# I2C_BUS.net
KiCad netlist of a schematic drawn in Altium Designer
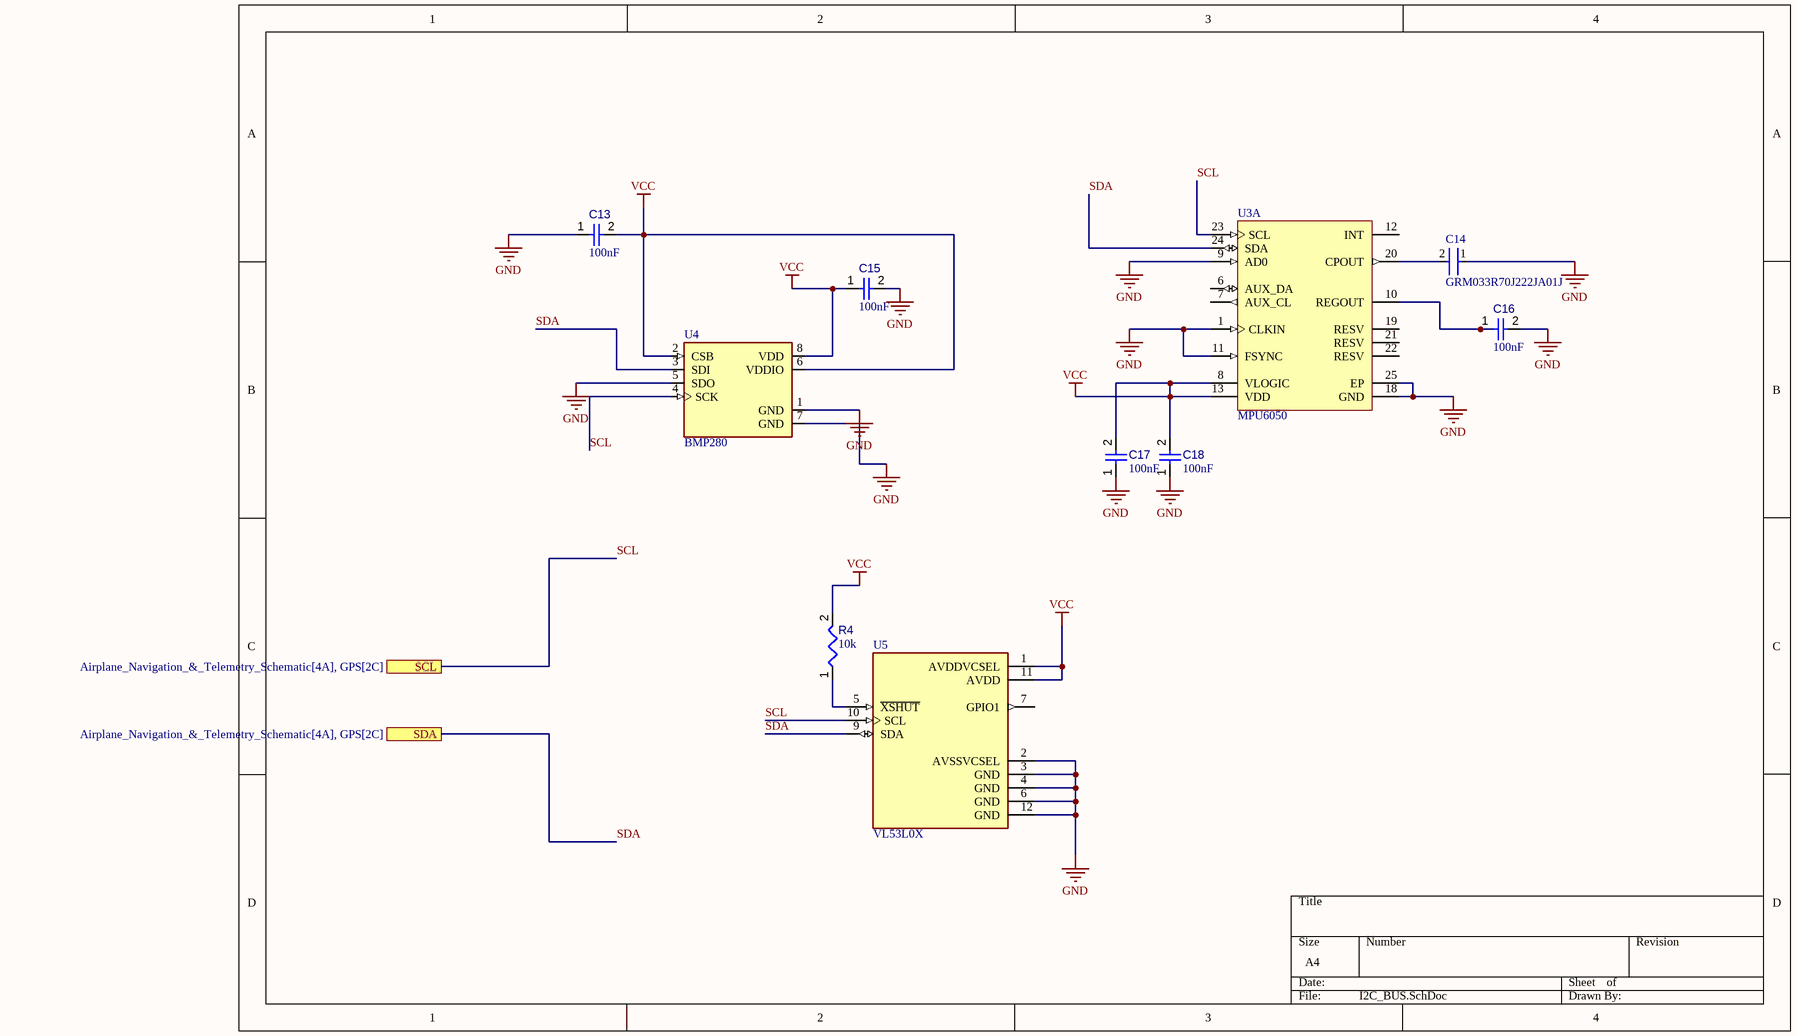
[diagram p0: I2C_BUS.SchDoc]

(export (version "E")
  (design (tool "Eeschema 10.0.6"))
  (components
    (comp (ref "C13")
      (value "100nF")
      (footprint "CAPC0402(1005)60_L")
      (description "Chip Capacitor, 100nF +/-20%, 10V, 0402, Thickness 0.6 mm")
      (fields (field (name "TOLERANCE") "20%") (field (name "Comment") "Capacitor 100nF +/-20% 10V 0402"))
      (libsource (lib "Lachlan Biersteker") (part "CAP-NP-2"))
    )
    (comp (ref "C14")
      (value "GRM033R70J222JA01J")
      (footprint "FP-GRM033-0_03-IPC_B")
      (description "Chip Multilayer Ceramic Capacitors for General Purpose, 0201, 2200pF, X7R, 15%, 5%, 6.3V")
      (fields (field (name "TOLERANCE") "5%"))
      (libsource (lib "Altium Content Vault") (part "b4654b650e69147ec39a6b967a45e02"))
    )
    (comp (ref "C15")
      (value "100nF")
      (footprint "CAPC0402(1005)60_L")
      (description "Chip Capacitor, 100nF +/-20%, 10V, 0402, Thickness 0.6 mm")
      (fields (field (name "TOLERANCE") "20%") (field (name "Comment") "Capacitor 100nF +/-20% 10V 0402"))
      (libsource (lib "Lachlan Biersteker") (part "CAP-NP-2"))
    )
    (comp (ref "C16")
      (value "100nF")
      (footprint "CAPC1005X56X25LL10T15")
      (description "Chip Capacitor, 0.1 uF, +/- 5%, 16 V, 0402 (1005 Metric)")
      (fields (field (name "TOLERANCE") "5%") (field (name "Comment") "Capacitor 0.1 uF +/- 5% 16 V 0402"))
      (libsource (lib "Lachlan Biersteker") (part "CAP-NP-2"))
    )
    (comp (ref "C17")
      (value "100nF")
      (footprint "CAPC0402(1005)60_L")
      (description "Chip Capacitor, 100nF +/-20%, 10V, 0402, Thickness 0.6 mm")
      (fields (field (name "TOLERANCE") "20%") (field (name "Comment") "Capacitor 100nF +/-20% 10V 0402"))
      (libsource (lib "Lachlan Biersteker") (part "CAP-NP-2"))
    )
    (comp (ref "C18")
      (value "100nF")
      (footprint "CAPC0402(1005)60_L")
      (description "Chip Capacitor, 100nF +/-20%, 10V, 0402, Thickness 0.6 mm")
      (fields (field (name "TOLERANCE") "20%") (field (name "Comment") "Capacitor 100nF +/-20% 10V 0402"))
      (libsource (lib "Lachlan Biersteker") (part "CAP-NP-2"))
    )
    (comp (ref "R4")
      (value "10k")
      (footprint "RESC1005X40X25ML05T05")
      (description "Chip Resistor, 10 KOhm, +/- 1%, 0.1 W, -55 to 155 degC, 0402 (1005 Metric)")
      (fields (field (name "TOLERANCE") "1%") (field (name "POWER") "100mW"))
      (libsource (lib "Lachlan Biersteker") (part "RES-2"))
    )
    (comp (ref "U3")
      (value "MPU6050")
      (footprint "INSE-QFN-24_V")
      (fields (field (name "MANUFACTURER") "InvenSense"))
      (libsource (lib "Lachlan Biersteker") (part "INSE-MPU6050-QFN-24"))
    )
    (comp (ref "U4")
      (value "BMP280")
      (footprint "XDCR_BMP280")
      (description "BMP280 Absolute Barometric Pressure Sensor for Battery Powered Devices 2 x 2.5mm")
      (libsource (lib "Lachlan Biersteker") (part "BMP280"))
    )
    (comp (ref "U5")
      (value "VL53L0X")
      (footprint "SENSOR_VL53L0X")
      (description "VL53L0X - Light, 3D Time-of-Flight _ToF_ Sensor Evaluation Board")
      (fields (field (name "MF") "STMicroelectronics"))
      (libsource (lib "Lachlan Biersteker") (part "VL53L0X"))
    )
  )
  (nets
    (net (code "1") (name "/SCL") (class "Default")
      (node (ref "U3") (pin "23") (pinfunction "SCL_23") (pintype "input"))
      (node (ref "U4") (pin "4") (pinfunction "SCK_4") (pintype "input"))
      (node (ref "U5") (pin "10") (pinfunction "SCL_10") (pintype "input"))
    )
    (net (code "2") (name "/SDA") (class "Default")
      (node (ref "U3") (pin "24") (pinfunction "SDA_24") (pintype "bidirectional"))
      (node (ref "U4") (pin "3") (pinfunction "SDI_3") (pintype "bidirectional"))
      (node (ref "U5") (pin "9") (pinfunction "SDA_9") (pintype "bidirectional"))
    )
    (net (code "3") (name "GND") (class "Default")
      (node (ref "C13") (pin "1") (pinfunction "1_1") (pintype "passive"))
      (node (ref "C14") (pin "1") (pinfunction "1_1") (pintype "passive"))
      (node (ref "C15") (pin "2") (pinfunction "2_2") (pintype "passive"))
      (node (ref "C16") (pin "2") (pinfunction "2_2") (pintype "passive"))
      (node (ref "C17") (pin "1") (pinfunction "1_1") (pintype "passive"))
      (node (ref "C18") (pin "1") (pinfunction "1_1") (pintype "passive"))
      (node (ref "U3") (pin "1") (pinfunction "CLKIN_1") (pintype "input"))
      (node (ref "U3") (pin "11") (pinfunction "FSYNC_11") (pintype "input"))
      (node (ref "U3") (pin "18") (pinfunction "GND_18") (pintype "power_in"))
      (node (ref "U3") (pin "25") (pinfunction "EP_25") (pintype "passive"))
      (node (ref "U3") (pin "9") (pinfunction "AD0_9") (pintype "input"))
      (node (ref "U4") (pin "1") (pinfunction "GND_1") (pintype "power_in"))
      (node (ref "U4") (pin "5") (pinfunction "SDO_5") (pintype "bidirectional"))
      (node (ref "U4") (pin "7") (pinfunction "GND_7") (pintype "power_in"))
      (node (ref "U5") (pin "12") (pinfunction "GND_12") (pintype "power_in"))
      (node (ref "U5") (pin "2") (pinfunction "AVSSVCSEL_2") (pintype "power_in"))
      (node (ref "U5") (pin "3") (pinfunction "GND_3") (pintype "power_in"))
      (node (ref "U5") (pin "4") (pinfunction "GND_4") (pintype "power_in"))
      (node (ref "U5") (pin "6") (pinfunction "GND_6") (pintype "power_in"))
    )
    (net (code "4") (name "Net-(U3A-CPOUT)") (class "Default")
      (node (ref "C14") (pin "2") (pinfunction "2_2") (pintype "passive"))
      (node (ref "U3") (pin "20") (pinfunction "CPOUT_20") (pintype "output"))
    )
    (net (code "5") (name "Net-(U3A-REGOUT)") (class "Default")
      (node (ref "C16") (pin "1") (pinfunction "1_1") (pintype "passive"))
      (node (ref "U3") (pin "10") (pinfunction "REGOUT_10") (pintype "passive"))
    )
    (net (code "6") (name "Net-(U5-~{XSHUT})") (class "Default")
      (node (ref "R4") (pin "1") (pinfunction "1_1") (pintype "passive"))
      (node (ref "U5") (pin "5") (pinfunction "~{XSHUT}_5") (pintype "input"))
    )
    (net (code "7") (name "VCC") (class "Default")
      (node (ref "C13") (pin "2") (pinfunction "2_2") (pintype "passive"))
      (node (ref "C15") (pin "1") (pinfunction "1_1") (pintype "passive"))
      (node (ref "C17") (pin "2") (pinfunction "2_2") (pintype "passive"))
      (node (ref "C18") (pin "2") (pinfunction "2_2") (pintype "passive"))
      (node (ref "R4") (pin "2") (pinfunction "2_2") (pintype "passive"))
      (node (ref "U3") (pin "13") (pinfunction "VDD_13") (pintype "power_in"))
      (node (ref "U3") (pin "8") (pinfunction "VLOGIC_8") (pintype "power_in"))
      (node (ref "U4") (pin "2") (pinfunction "CSB_2") (pintype "input"))
      (node (ref "U4") (pin "6") (pinfunction "VDDIO_6") (pintype "power_in"))
      (node (ref "U4") (pin "8") (pinfunction "VDD_8") (pintype "power_in"))
      (node (ref "U5") (pin "1") (pinfunction "AVDDVCSEL_1") (pintype "power_in"))
      (node (ref "U5") (pin "11") (pinfunction "AVDD_11") (pintype "power_in"))
    )
    (net (code "8") (name "unconnected-(U3A-AUX_CL-Pad7)") (class "Default")
      (node (ref "U3") (pin "7") (pinfunction "AUX_CL_7") (pintype "output"))
    )
    (net (code "9") (name "unconnected-(U3A-AUX_DA-Pad6)") (class "Default")
      (node (ref "U3") (pin "6") (pinfunction "AUX_DA_6") (pintype "bidirectional"))
    )
    (net (code "10") (name "unconnected-(U3A-INT-Pad12)") (class "Default")
      (node (ref "U3") (pin "12") (pinfunction "INT_12") (pintype "open_collector"))
    )
    (net (code "11") (name "unconnected-(U3A-RESV-Pad19)") (class "Default")
      (node (ref "U3") (pin "19") (pinfunction "RESV_19") (pintype "passive"))
    )
    (net (code "12") (name "unconnected-(U3A-RESV-Pad21)") (class "Default")
      (node (ref "U3") (pin "21") (pinfunction "RESV_21") (pintype "passive"))
    )
    (net (code "13") (name "unconnected-(U3A-RESV-Pad22)") (class "Default")
      (node (ref "U3") (pin "22") (pinfunction "RESV_22") (pintype "passive"))
    )
    (net (code "14") (name "unconnected-(U5-GPIO1-Pad7)") (class "Default")
      (node (ref "U5") (pin "7") (pinfunction "GPIO1_7") (pintype "output"))
    )
  )
)
